# hb-featherwing.net
KiCad netlist of a schematic drawn in EAGLE
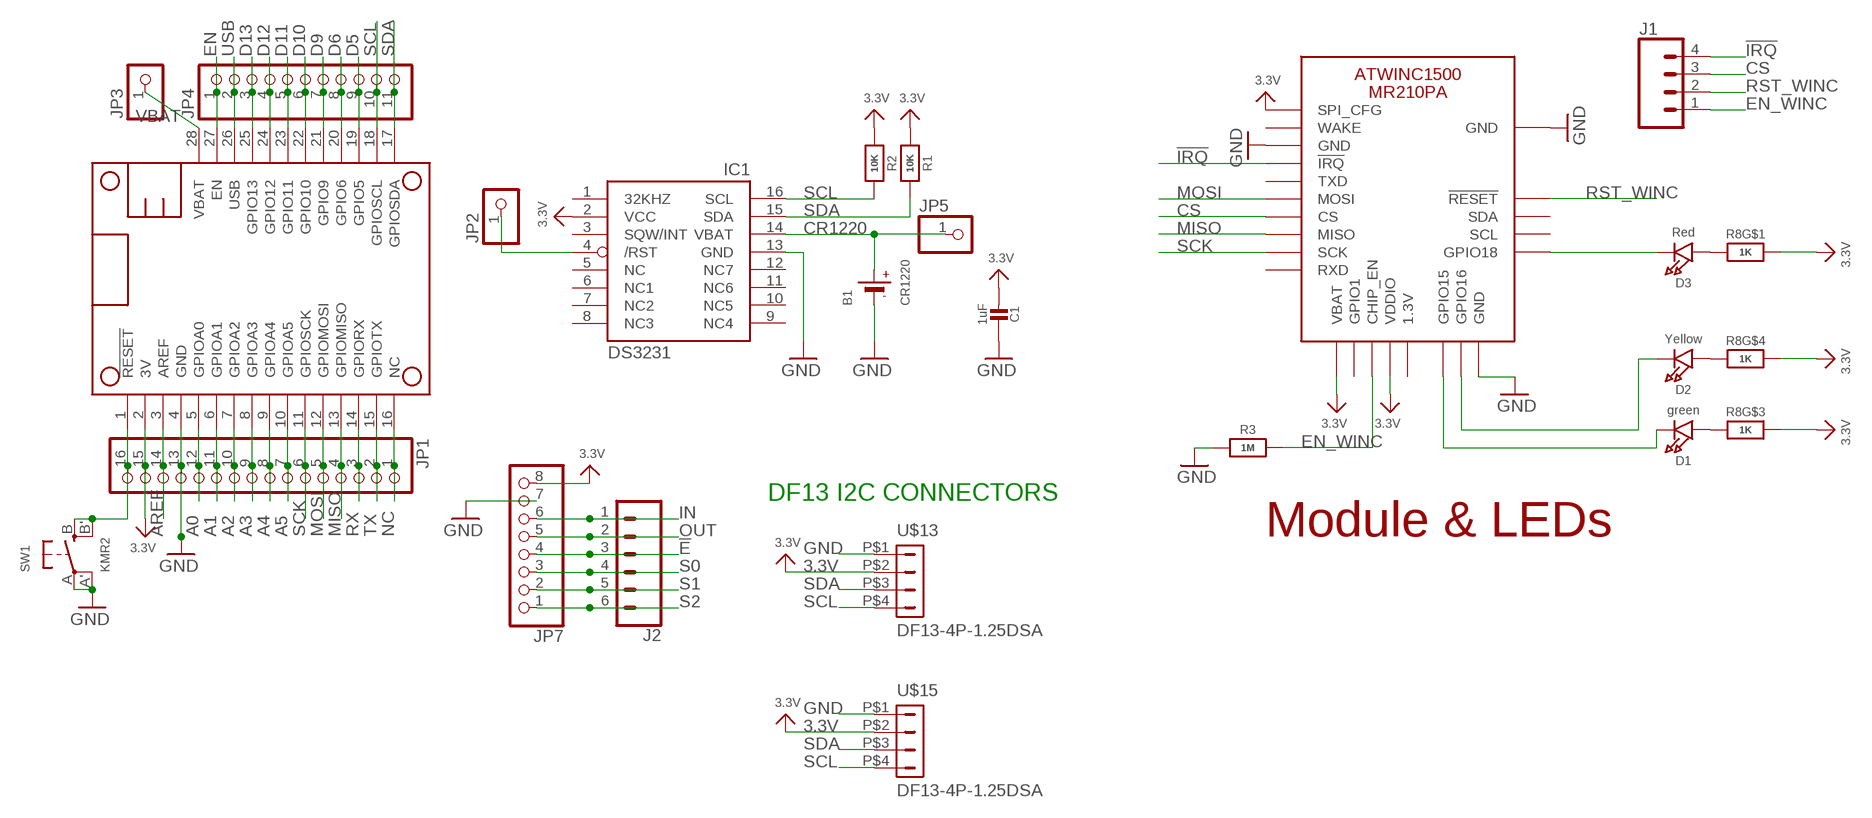
[diagram p0: schematic, sheet 1]

(export (version "E")
  (design (tool "Eeschema 10.0.6"))
  (components
    (comp (ref "B1")
      (value "CR1220")
      (footprint "eagle-import:CR1220-2")
      (libsource (lib "eagle-import") (part "BATTERYCR1220_2"))
    )
    (comp (ref "C1")
      (value "1uF")
      (footprint "eagle-import:0805-NO")
      (libsource (lib "eagle-import") (part "CAP_CERAMIC0805-NOOUTLINE"))
    )
    (comp (ref "D1")
      (value "green")
      (footprint "eagle-import:CHIPLED_0805_NOOUTLINE")
      (libsource (lib "eagle-import") (part "LED0805_NOOUTLINE"))
    )
    (comp (ref "D2")
      (value "Yellow")
      (footprint "eagle-import:CHIPLED_0805_NOOUTLINE")
      (libsource (lib "eagle-import") (part "LED0805_NOOUTLINE"))
    )
    (comp (ref "D3")
      (value "Red")
      (footprint "eagle-import:CHIPLED_0805_NOOUTLINE")
      (libsource (lib "eagle-import") (part "LED0805_NOOUTLINE"))
    )
    (comp (ref "IC1")
      (value "DS3231/SO")
      (footprint "eagle-import:SO16W")
      (libsource (lib "eagle-import") (part "DS3231/SO"))
    )
    (comp (ref "J1")
      (value "CONN_04")
      (footprint "eagle-import:1X04")
      (libsource (lib "eagle-import") (part "CONN_04"))
    )
    (comp (ref "J2")
      (value "CONN_06SILK_FEMALE_PTH")
      (footprint "eagle-import:1X06")
      (libsource (lib "eagle-import") (part "CONN_06SILK_FEMALE_PTH"))
    )
    (comp (ref "JP1")
      (value "HEADER-1X16ROUND")
      (footprint "eagle-import:1X16_ROUND")
      (libsource (lib "eagle-import") (part "HEADER-1X16ROUND"))
    )
    (comp (ref "JP2")
      (value "HEADER-1X1ROUND")
      (footprint "eagle-import:1X01_ROUND")
      (libsource (lib "eagle-import") (part "HEADER-1X1ROUND"))
    )
    (comp (ref "JP3")
      (value "HEADER-1X1ROUND")
      (footprint "eagle-import:1X01_ROUND")
      (libsource (lib "eagle-import") (part "HEADER-1X1ROUND"))
    )
    (comp (ref "JP4")
      (value "HEADER-1X11")
      (footprint "eagle-import:1X11_ROUND")
      (libsource (lib "eagle-import") (part "HEADER-1X11"))
    )
    (comp (ref "JP5")
      (value "HEADER-1X1ROUND")
      (footprint "eagle-import:1X01_ROUND")
      (libsource (lib "eagle-import") (part "HEADER-1X1ROUND"))
    )
    (comp (ref "JP7")
      (value "PINHD-1X8BIG")
      (footprint "eagle-import:1X08-BIG")
      (libsource (lib "eagle-import") (part "PINHD-1X8BIG"))
    )
    (comp (ref "MS1")
      (value "MICROSHIELD_NODIM")
      (footprint "eagle-import:MICROSHIELD_DIM")
      (libsource (lib "eagle-import") (part "MICROSHIELD_NODIM"))
    )
    (comp (ref "R1")
      (value "10K")
      (footprint "eagle-import:0805-NO")
      (libsource (lib "eagle-import") (part "RESISTOR0805_NOOUTLINE"))
    )
    (comp (ref "R2")
      (value "10K")
      (footprint "eagle-import:0805-NO")
      (libsource (lib "eagle-import") (part "RESISTOR0805_NOOUTLINE"))
    )
    (comp (ref "R3")
      (value "1M")
      (footprint "eagle-import:0805-NO")
      (libsource (lib "eagle-import") (part "RESISTOR0805_NOOUTLINE"))
    )
    (comp (ref "R8")
      (value "1K")
      (footprint "eagle-import:RESPACK_4X0603")
      (libsource (lib "eagle-import") (part "RESISTOR_4PACK"))
    )
    (comp (ref "SW1")
      (value "KMR2")
      (footprint "eagle-import:BTN_KMR2_4.6X2.8")
      (libsource (lib "eagle-import") (part "SWITCH_TACT_SMT4.6X2.8"))
    )
    (comp (ref "U$7")
      (value "ATWINC1500_MR210PB")
      (footprint "eagle-import:ATWINC1500_MR210PA")
      (libsource (lib "eagle-import") (part "ATWINC1500_MR210PA"))
    )
    (comp (ref "U$13")
      (value "DF13-4P-1.25DSA")
      (footprint "eagle-import:DF13-4P-1.25DSA")
      (libsource (lib "eagle-import") (part "DF13-4P-1.25DSA"))
    )
    (comp (ref "U$15")
      (value "DF13-4P-1.25DSA")
      (footprint "eagle-import:DF13-4P-1.25DSA")
      (libsource (lib "eagle-import") (part "DF13-4P-1.25DSA"))
    )
  )
  (nets
    (net (code "1") (name "/A0") (class "Default")
      (node (ref "JP1") (pin "12") (pinfunction "12_12") (pintype "passive"))
      (node (ref "MS1") (pin "5") (pinfunction "GPIOA0_5") (pintype "bidirectional"))
    )
    (net (code "2") (name "/A1") (class "Default")
      (node (ref "JP1") (pin "11") (pinfunction "11_11") (pintype "passive"))
      (node (ref "MS1") (pin "6") (pinfunction "GPIOA1_6") (pintype "bidirectional"))
    )
    (net (code "3") (name "/A2") (class "Default")
      (node (ref "JP1") (pin "10") (pinfunction "10_10") (pintype "passive"))
      (node (ref "MS1") (pin "7") (pinfunction "GPIOA2_7") (pintype "bidirectional"))
    )
    (net (code "4") (name "/A3") (class "Default")
      (node (ref "JP1") (pin "9") (pinfunction "9_9") (pintype "passive"))
      (node (ref "MS1") (pin "8") (pinfunction "GPIOA3_8") (pintype "bidirectional"))
    )
    (net (code "5") (name "/A4") (class "Default")
      (node (ref "JP1") (pin "8") (pinfunction "8_8") (pintype "passive"))
      (node (ref "MS1") (pin "9") (pinfunction "GPIOA4_9") (pintype "bidirectional"))
    )
    (net (code "6") (name "/A5") (class "Default")
      (node (ref "JP1") (pin "7") (pinfunction "7_7") (pintype "passive"))
      (node (ref "MS1") (pin "10") (pinfunction "GPIOA5_10") (pintype "bidirectional"))
    )
    (net (code "7") (name "/AREF") (class "Default")
      (node (ref "JP1") (pin "14") (pinfunction "14_14") (pintype "passive"))
      (node (ref "MS1") (pin "3") (pinfunction "AREF_3") (pintype "passive"))
    )
    (net (code "8") (name "/CR1220") (class "Default")
      (node (ref "B1") (pin "+") (pinfunction "+_+") (pintype "passive"))
      (node (ref "IC1") (pin "14") (pinfunction "VBAT_14") (pintype "power_in"))
      (node (ref "JP5") (pin "1") (pinfunction "1_1") (pintype "passive"))
    )
    (net (code "9") (name "/CS") (class "Default")
      (node (ref "J1") (pin "3") (pinfunction "3_3") (pintype "passive"))
      (node (ref "U$7") (pin "J16") (pinfunction "CS_J16") (pintype "input"))
    )
    (net (code "10") (name "/D5") (class "Default")
      (node (ref "JP4") (pin "9") (pinfunction "9_9") (pintype "passive"))
      (node (ref "MS1") (pin "19") (pinfunction "GPIO5_19") (pintype "bidirectional"))
    )
    (net (code "11") (name "/D6") (class "Default")
      (node (ref "JP4") (pin "8") (pinfunction "8_8") (pintype "passive"))
      (node (ref "MS1") (pin "20") (pinfunction "GPIO6_20") (pintype "bidirectional"))
    )
    (net (code "12") (name "/D9") (class "Default")
      (node (ref "JP4") (pin "7") (pinfunction "7_7") (pintype "passive"))
      (node (ref "MS1") (pin "21") (pinfunction "GPIO9_21") (pintype "bidirectional"))
    )
    (net (code "13") (name "/D10") (class "Default")
      (node (ref "JP4") (pin "6") (pinfunction "6_6") (pintype "passive"))
      (node (ref "MS1") (pin "22") (pinfunction "GPIO10_22") (pintype "bidirectional"))
    )
    (net (code "14") (name "/D11") (class "Default")
      (node (ref "JP4") (pin "5") (pinfunction "5_5") (pintype "passive"))
      (node (ref "MS1") (pin "23") (pinfunction "GPIO11_23") (pintype "bidirectional"))
    )
    (net (code "15") (name "/D12") (class "Default")
      (node (ref "JP4") (pin "4") (pinfunction "4_4") (pintype "passive"))
      (node (ref "MS1") (pin "24") (pinfunction "GPIO12_24") (pintype "bidirectional"))
    )
    (net (code "16") (name "/D13") (class "Default")
      (node (ref "JP4") (pin "3") (pinfunction "3_3") (pintype "passive"))
      (node (ref "MS1") (pin "25") (pinfunction "GPIO13_25") (pintype "bidirectional"))
    )
    (net (code "17") (name "/EN") (class "Default")
      (node (ref "JP4") (pin "1") (pinfunction "1_1") (pintype "passive"))
      (node (ref "MS1") (pin "27") (pinfunction "EN_27") (pintype "passive"))
    )
    (net (code "18") (name "/EN_WINC") (class "Default")
      (node (ref "J1") (pin "1") (pinfunction "1_1") (pintype "passive"))
      (node (ref "R3") (pin "2") (pinfunction "2_2") (pintype "passive"))
      (node (ref "U$7") (pin "J22") (pinfunction "CHIP_EN_J22") (pintype "input"))
    )
    (net (code "19") (name "/IN") (class "Default")
      (node (ref "J2") (pin "1") (pinfunction "1_1") (pintype "passive"))
      (node (ref "JP7") (pin "6") (pinfunction "6_6") (pintype "passive"))
    )
    (net (code "20") (name "/MISO") (class "Default")
      (node (ref "JP1") (pin "4") (pinfunction "4_4") (pintype "passive"))
      (node (ref "MS1") (pin "13") (pinfunction "GPIOMISO_13") (pintype "bidirectional"))
      (node (ref "U$7") (pin "J17") (pinfunction "MISO_J17") (pintype "output"))
    )
    (net (code "21") (name "/MOSI") (class "Default")
      (node (ref "JP1") (pin "5") (pinfunction "5_5") (pintype "passive"))
      (node (ref "MS1") (pin "12") (pinfunction "GPIOMOSI_12") (pintype "bidirectional"))
      (node (ref "U$7") (pin "J15") (pinfunction "MOSI_J15") (pintype "input"))
    )
    (net (code "22") (name "/NC") (class "Default")
      (node (ref "JP1") (pin "1") (pinfunction "1_1") (pintype "passive"))
      (node (ref "MS1") (pin "16") (pinfunction "NC_16") (pintype "passive"))
    )
    (net (code "23") (name "/OUT") (class "Default")
      (node (ref "J2") (pin "2") (pinfunction "2_2") (pintype "passive"))
      (node (ref "JP7") (pin "5") (pinfunction "5_5") (pintype "passive"))
    )
    (net (code "24") (name "/RST_WINC") (class "Default")
      (node (ref "J1") (pin "2") (pinfunction "2_2") (pintype "passive"))
      (node (ref "U$7") (pin "J4") (pinfunction "~{RESET}_J4") (pintype "input"))
    )
    (net (code "25") (name "/RX") (class "Default")
      (node (ref "JP1") (pin "3") (pinfunction "3_3") (pintype "passive"))
      (node (ref "MS1") (pin "14") (pinfunction "GPIORX_14") (pintype "bidirectional"))
    )
    (net (code "26") (name "/S0") (class "Default")
      (node (ref "J2") (pin "4") (pinfunction "4_4") (pintype "passive"))
      (node (ref "JP7") (pin "3") (pinfunction "3_3") (pintype "passive"))
    )
    (net (code "27") (name "/S1") (class "Default")
      (node (ref "J2") (pin "5") (pinfunction "5_5") (pintype "passive"))
      (node (ref "JP7") (pin "2") (pinfunction "2_2") (pintype "passive"))
    )
    (net (code "28") (name "/S2") (class "Default")
      (node (ref "J2") (pin "6") (pinfunction "6_6") (pintype "passive"))
      (node (ref "JP7") (pin "1") (pinfunction "1_1") (pintype "passive"))
    )
    (net (code "29") (name "/SCK") (class "Default")
      (node (ref "JP1") (pin "6") (pinfunction "6_6") (pintype "passive"))
      (node (ref "MS1") (pin "11") (pinfunction "GPIOSCK_11") (pintype "bidirectional"))
      (node (ref "U$7") (pin "J18") (pinfunction "SCK_J18") (pintype "input"))
    )
    (net (code "30") (name "/SCL") (class "Default")
      (node (ref "IC1") (pin "16") (pinfunction "SCL_16") (pintype "bidirectional"))
      (node (ref "JP4") (pin "10") (pinfunction "10_10") (pintype "passive"))
      (node (ref "MS1") (pin "18") (pinfunction "GPIOSCL_18") (pintype "bidirectional"))
      (node (ref "R2") (pin "2") (pinfunction "2_2") (pintype "passive"))
      (node (ref "U$13") (pin "P$4") (pinfunction "4_P$4") (pintype "passive"))
      (node (ref "U$15") (pin "P$4") (pinfunction "4_P$4") (pintype "passive"))
    )
    (net (code "31") (name "/SDA") (class "Default")
      (node (ref "IC1") (pin "15") (pinfunction "SDA_15") (pintype "bidirectional"))
      (node (ref "JP4") (pin "11") (pinfunction "11_11") (pintype "passive"))
      (node (ref "MS1") (pin "17") (pinfunction "GPIOSDA_17") (pintype "bidirectional"))
      (node (ref "R1") (pin "2") (pinfunction "2_2") (pintype "passive"))
      (node (ref "U$13") (pin "P$3") (pinfunction "3_P$3") (pintype "passive"))
      (node (ref "U$15") (pin "P$3") (pinfunction "3_P$3") (pintype "passive"))
    )
    (net (code "32") (name "/TX") (class "Default")
      (node (ref "JP1") (pin "2") (pinfunction "2_2") (pintype "passive"))
      (node (ref "MS1") (pin "15") (pinfunction "GPIOTX_15") (pintype "bidirectional"))
    )
    (net (code "33") (name "/USB") (class "Default")
      (node (ref "JP4") (pin "2") (pinfunction "2_2") (pintype "passive"))
      (node (ref "MS1") (pin "26") (pinfunction "USB_26") (pintype "power_in"))
    )
    (net (code "34") (name "/VBAT") (class "Default")
      (node (ref "JP3") (pin "1") (pinfunction "1_1") (pintype "passive"))
      (node (ref "MS1") (pin "28") (pinfunction "VBAT_28") (pintype "power_in"))
    )
    (net (code "35") (name "/~{E}") (class "Default")
      (node (ref "J2") (pin "3") (pinfunction "3_3") (pintype "passive"))
      (node (ref "JP7") (pin "4") (pinfunction "4_4") (pintype "passive"))
    )
    (net (code "36") (name "/~{IRQ}") (class "Default")
      (node (ref "J1") (pin "4") (pinfunction "4_4") (pintype "passive"))
      (node (ref "U$7") (pin "J13") (pinfunction "~{IRQ}_J13") (pintype "output"))
    )
    (net (code "37") (name "3.3V") (class "Default")
      (node (ref "C1") (pin "2") (pinfunction "2_2") (pintype "passive"))
      (node (ref "IC1") (pin "2") (pinfunction "VCC_2") (pintype "power_in"))
      (node (ref "JP1") (pin "15") (pinfunction "15_15") (pintype "passive"))
      (node (ref "JP7") (pin "8") (pinfunction "8_8") (pintype "passive"))
      (node (ref "MS1") (pin "2") (pinfunction "3V_2") (pintype "power_in"))
      (node (ref "R1") (pin "1") (pinfunction "1_1") (pintype "passive"))
      (node (ref "R2") (pin "1") (pinfunction "1_1") (pintype "passive"))
      (node (ref "R8") (pin "5") (pinfunction "2_5") (pintype "passive"))
      (node (ref "R8") (pin "6") (pinfunction "2_6") (pintype "passive"))
      (node (ref "R8") (pin "8") (pinfunction "2_8") (pintype "passive"))
      (node (ref "U$13") (pin "P$2") (pinfunction "2_P$2") (pintype "passive"))
      (node (ref "U$15") (pin "P$2") (pinfunction "2_P$2") (pintype "passive"))
      (node (ref "U$7") (pin "J10") (pinfunction "SPI_CFG_J10") (pintype "input"))
      (node (ref "U$7") (pin "J20") (pinfunction "VBAT_J20") (pintype "power_in"))
      (node (ref "U$7") (pin "J23") (pinfunction "VDDIO_J23") (pintype "power_in"))
    )
    (net (code "38") (name "GND") (class "Default")
      (node (ref "B1") (pin "-") (pinfunction "-_-") (pintype "passive"))
      (node (ref "C1") (pin "1") (pinfunction "1_1") (pintype "passive"))
      (node (ref "IC1") (pin "13") (pinfunction "GND_13") (pintype "power_in"))
      (node (ref "JP1") (pin "13") (pinfunction "13_13") (pintype "passive"))
      (node (ref "JP7") (pin "7") (pinfunction "7_7") (pintype "passive"))
      (node (ref "MS1") (pin "4") (pinfunction "GND_4") (pintype "power_in"))
      (node (ref "R3") (pin "1") (pinfunction "1_1") (pintype "passive"))
      (node (ref "SW1") (pin "A") (pinfunction "P_A") (pintype "passive"))
      (node (ref "SW1") (pin "A'") (pinfunction "P1_A'") (pintype "passive"))
      (node (ref "U$13") (pin "P$1") (pinfunction "1_P$1") (pintype "passive"))
      (node (ref "U$15") (pin "P$1") (pinfunction "1_P$1") (pintype "passive"))
      (node (ref "U$7") (pin "J12") (pinfunction "GND_J12") (pintype "power_in"))
      (node (ref "U$7") (pin "J28") (pinfunction "GND_J28") (pintype "power_in"))
      (node (ref "U$7") (pin "J9") (pinfunction "GND_J9") (pintype "bidirectional"))
      (node (ref "U$7") (pin "MTGND") (pinfunction "GND_MTGND") (pintype "power_in"))
    )
    (net (code "39") (name "Net-(D3-PadA)") (class "Default")
      (node (ref "D3") (pin "A") (pinfunction "A_A") (pintype "passive"))
      (node (ref "R8") (pin "1") (pinfunction "1_1") (pintype "passive"))
    )
    (net (code "40") (name "Net-(IC1-{slash}RST)") (class "Default")
      (node (ref "IC1") (pin "4") (pinfunction "/RST_4") (pintype "passive"))
      (node (ref "JP2") (pin "1") (pinfunction "1_1") (pintype "passive"))
    )
    (net (code "41") (name "Net-(MS1-~{RESET})") (class "Default")
      (node (ref "JP1") (pin "16") (pinfunction "16_16") (pintype "passive"))
      (node (ref "MS1") (pin "1") (pinfunction "~{RESET}_1") (pintype "input"))
      (node (ref "SW1") (pin "B") (pinfunction "S_B") (pintype "passive"))
      (node (ref "SW1") (pin "B'") (pinfunction "S1_B'") (pintype "passive"))
    )
    (net (code "42") (name "Net-(R8C-1)") (class "Default")
      (node (ref "D1") (pin "A") (pinfunction "A_A") (pintype "passive"))
      (node (ref "R8") (pin "3") (pinfunction "1_3") (pintype "passive"))
    )
    (net (code "43") (name "Net-(R8D-1)") (class "Default")
      (node (ref "D2") (pin "A") (pinfunction "A_A") (pintype "passive"))
      (node (ref "R8") (pin "4") (pinfunction "1_4") (pintype "passive"))
    )
    (net (code "44") (name "Net-(U$7-GPIO15)") (class "Default")
      (node (ref "D1") (pin "C") (pinfunction "C_C") (pintype "passive"))
      (node (ref "U$7") (pin "J26") (pinfunction "GPIO15_J26") (pintype "bidirectional"))
    )
    (net (code "45") (name "Net-(U$7-GPIO16)") (class "Default")
      (node (ref "D2") (pin "C") (pinfunction "C_C") (pintype "passive"))
      (node (ref "U$7") (pin "J27") (pinfunction "GPIO16_J27") (pintype "bidirectional"))
    )
    (net (code "46") (name "Net-(U$7-GPIO18)") (class "Default")
      (node (ref "D3") (pin "C") (pinfunction "C_C") (pintype "passive"))
      (node (ref "U$7") (pin "J1") (pinfunction "GPIO18_J1") (pintype "bidirectional"))
    )
    (net (code "47") (name "unconnected-(IC1-32KHZ-Pad1)") (class "Default")
      (node (ref "IC1") (pin "1") (pinfunction "32KHZ_1") (pintype "output"))
    )
    (net (code "48") (name "unconnected-(IC1-NC-Pad5)") (class "Default")
      (node (ref "IC1") (pin "5") (pinfunction "NC_5") (pintype "no_connect"))
    )
    (net (code "49") (name "unconnected-(IC1-NC1-Pad6)") (class "Default")
      (node (ref "IC1") (pin "6") (pinfunction "NC1_6") (pintype "no_connect"))
    )
    (net (code "50") (name "unconnected-(IC1-NC2-Pad7)") (class "Default")
      (node (ref "IC1") (pin "7") (pinfunction "NC2_7") (pintype "no_connect"))
    )
    (net (code "51") (name "unconnected-(IC1-NC3-Pad8)") (class "Default")
      (node (ref "IC1") (pin "8") (pinfunction "NC3_8") (pintype "no_connect"))
    )
    (net (code "52") (name "unconnected-(IC1-NC4-Pad9)") (class "Default")
      (node (ref "IC1") (pin "9") (pinfunction "NC4_9") (pintype "no_connect"))
    )
    (net (code "53") (name "unconnected-(IC1-NC5-Pad10)") (class "Default")
      (node (ref "IC1") (pin "10") (pinfunction "NC5_10") (pintype "no_connect"))
    )
    (net (code "54") (name "unconnected-(IC1-NC6-Pad11)") (class "Default")
      (node (ref "IC1") (pin "11") (pinfunction "NC6_11") (pintype "no_connect"))
    )
    (net (code "55") (name "unconnected-(IC1-NC7-Pad12)") (class "Default")
      (node (ref "IC1") (pin "12") (pinfunction "NC7_12") (pintype "no_connect"))
    )
    (net (code "56") (name "unconnected-(IC1-SQW{slash}INT-Pad3)") (class "Default")
      (node (ref "IC1") (pin "3") (pinfunction "SQW/INT_3") (pintype "output"))
    )
    (net (code "57") (name "unconnected-(U$7-1.3V-PadJ24)") (class "Default")
      (node (ref "U$7") (pin "J24") (pinfunction "1.3V_J24") (pintype "passive"))
    )
    (net (code "58") (name "unconnected-(U$7-GPIO1-PadJ21)") (class "Default")
      (node (ref "U$7") (pin "J21") (pinfunction "GPIO1_J21") (pintype "bidirectional"))
    )
    (net (code "59") (name "unconnected-(U$7-RXD-PadJ19)") (class "Default")
      (node (ref "U$7") (pin "J19") (pinfunction "RXD_J19") (pintype "input"))
    )
    (net (code "60") (name "unconnected-(U$7-SCL-PadJ2)") (class "Default")
      (node (ref "U$7") (pin "J2") (pinfunction "SCL_J2") (pintype "bidirectional"))
    )
    (net (code "61") (name "unconnected-(U$7-SDA-PadJ3)") (class "Default")
      (node (ref "U$7") (pin "J3") (pinfunction "SDA_J3") (pintype "bidirectional"))
    )
    (net (code "62") (name "unconnected-(U$7-TXD-PadJ14)") (class "Default")
      (node (ref "U$7") (pin "J14") (pinfunction "TXD_J14") (pintype "output"))
    )
    (net (code "63") (name "unconnected-(U$7-WAKE-PadJ11)") (class "Default")
      (node (ref "U$7") (pin "J11") (pinfunction "WAKE_J11") (pintype "input"))
    )
  )
)
